# esp_LedControl_signal.net
KiCad netlist of a schematic drawn in EAGLE
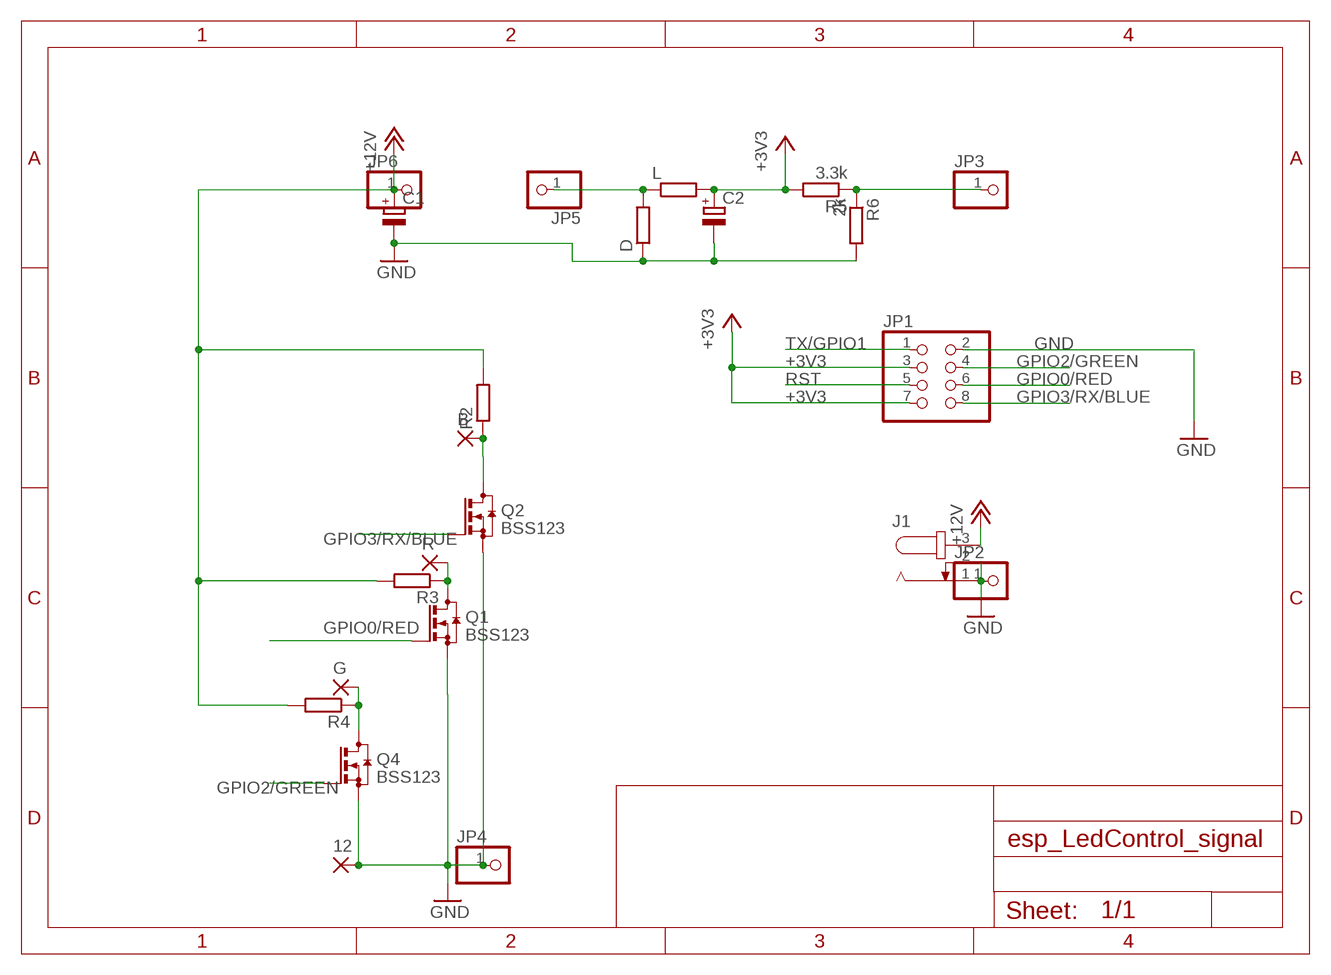
[diagram p0: schematic, sheet 1]

(export (version "E")
  (design (tool "Eeschema 10.0.6"))
  (components
    (comp (ref "12")
      (value "3,17/1,3")
      (footprint "eagle-import:3,17_1,3")
      (libsource (lib "eagle-import") (part "3,17/1,3"))
    )
    (comp (ref "B")
      (value "3,17/1,3")
      (footprint "eagle-import:3,17_1,3")
      (libsource (lib "eagle-import") (part "3,17/1,3"))
    )
    (comp (ref "C1")
      (value "CPOL-EUE2.5-5")
      (footprint "eagle-import:E2,5-5")
      (libsource (lib "eagle-import") (part "CPOL-EUE2.5-5"))
    )
    (comp (ref "C2")
      (value "CPOL-EUE2.5-5")
      (footprint "eagle-import:E2,5-5")
      (libsource (lib "eagle-import") (part "CPOL-EUE2.5-5"))
    )
    (comp (ref "D")
      (value "R-EU_0204/7")
      (footprint "eagle-import:0204_7")
      (libsource (lib "eagle-import") (part "R-EU_0204/7"))
    )
    (comp (ref "G")
      (value "3,17/1,3")
      (footprint "eagle-import:3,17_1,3")
      (libsource (lib "eagle-import") (part "3,17/1,3"))
    )
    (comp (ref "J1")
      (value "JACK-PLUG0")
      (footprint "eagle-import:SPC4077")
      (libsource (lib "eagle-import") (part "JACK-PLUG0"))
    )
    (comp (ref "JP1")
      (value "PINHD-2X4")
      (footprint "eagle-import:2X04")
      (libsource (lib "eagle-import") (part "PINHD-2X4"))
    )
    (comp (ref "JP2")
      (value "PINHD-1X1")
      (footprint "eagle-import:1X01")
      (libsource (lib "eagle-import") (part "PINHD-1X1"))
    )
    (comp (ref "JP3")
      (value "PINHD-1X1")
      (footprint "eagle-import:1X01")
      (libsource (lib "eagle-import") (part "PINHD-1X1"))
    )
    (comp (ref "JP4")
      (value "PINHD-1X1")
      (footprint "eagle-import:1X01")
      (libsource (lib "eagle-import") (part "PINHD-1X1"))
    )
    (comp (ref "JP5")
      (value "PINHD-1X1")
      (footprint "eagle-import:1X01")
      (libsource (lib "eagle-import") (part "PINHD-1X1"))
    )
    (comp (ref "JP6")
      (value "PINHD-1X1")
      (footprint "eagle-import:1X01")
      (libsource (lib "eagle-import") (part "PINHD-1X1"))
    )
    (comp (ref "L")
      (value "R-EU_0204/7")
      (footprint "eagle-import:0204_7")
      (libsource (lib "eagle-import") (part "R-EU_0204/7"))
    )
    (comp (ref "Q1")
      (value "BSS123")
      (footprint "eagle-import:SOT23")
      (libsource (lib "eagle-import") (part "BSS123"))
    )
    (comp (ref "Q2")
      (value "BSS123")
      (footprint "eagle-import:SOT23")
      (libsource (lib "eagle-import") (part "BSS123"))
    )
    (comp (ref "Q4")
      (value "BSS123")
      (footprint "eagle-import:SOT23")
      (libsource (lib "eagle-import") (part "BSS123"))
    )
    (comp (ref "R")
      (value "3,17/1,3")
      (footprint "eagle-import:3,17_1,3")
      (libsource (lib "eagle-import") (part "3,17/1,3"))
    )
    (comp (ref "R2")
      (value "R-EU_R0805")
      (footprint "eagle-import:R0805")
      (libsource (lib "eagle-import") (part "R-EU_R0805"))
    )
    (comp (ref "R3")
      (value "R-EU_R0805")
      (footprint "eagle-import:R0805")
      (libsource (lib "eagle-import") (part "R-EU_R0805"))
    )
    (comp (ref "R4")
      (value "R-EU_R0805")
      (footprint "eagle-import:R0805")
      (libsource (lib "eagle-import") (part "R-EU_R0805"))
    )
    (comp (ref "R5")
      (value "3.3k")
      (footprint "eagle-import:R1206")
      (libsource (lib "eagle-import") (part "R-EU_R1206"))
    )
    (comp (ref "R6")
      (value "2k")
      (footprint "eagle-import:R1206")
      (libsource (lib "eagle-import") (part "R-EU_R1206"))
    )
  )
  (nets
    (net (code "1") (name "+3V3") (class "Default")
      (node (ref "C2") (pin "+") (pinfunction "+_+") (pintype "passive"))
      (node (ref "JP1") (pin "3") (pinfunction "3_3") (pintype "passive"))
      (node (ref "JP1") (pin "7") (pinfunction "7_7") (pintype "passive"))
      (node (ref "L") (pin "2") (pinfunction "2_2") (pintype "passive"))
      (node (ref "R5") (pin "2") (pinfunction "2_2") (pintype "passive"))
    )
    (net (code "2") (name "+12V") (class "Default")
      (node (ref "C1") (pin "+") (pinfunction "+_+") (pintype "passive"))
      (node (ref "J1") (pin "3") (pinfunction "3_3") (pintype "passive"))
      (node (ref "JP6") (pin "1") (pinfunction "1_1") (pintype "passive"))
      (node (ref "R2") (pin "2") (pinfunction "2_2") (pintype "passive"))
      (node (ref "R3") (pin "2") (pinfunction "2_2") (pintype "passive"))
      (node (ref "R4") (pin "2") (pinfunction "2_2") (pintype "passive"))
    )
    (net (code "3") (name "/GPIO0{slash}RED") (class "Default")
      (node (ref "JP1") (pin "6") (pinfunction "6_6") (pintype "passive"))
      (node (ref "Q1") (pin "1") (pinfunction "G_1") (pintype "passive"))
    )
    (net (code "4") (name "/GPIO2{slash}GREEN") (class "Default")
      (node (ref "JP1") (pin "4") (pinfunction "4_4") (pintype "passive"))
      (node (ref "Q4") (pin "1") (pinfunction "G_1") (pintype "passive"))
    )
    (net (code "5") (name "/GPIO3{slash}RX{slash}BLUE") (class "Default")
      (node (ref "JP1") (pin "8") (pinfunction "8_8") (pintype "passive"))
      (node (ref "Q2") (pin "1") (pinfunction "G_1") (pintype "passive"))
    )
    (net (code "6") (name "/RST") (class "Default")
      (node (ref "JP1") (pin "5") (pinfunction "5_5") (pintype "passive"))
    )
    (net (code "7") (name "/TX{slash}GPIO1") (class "Default")
      (node (ref "JP1") (pin "1") (pinfunction "1_1") (pintype "passive"))
    )
    (net (code "8") (name "GND") (class "Default")
      (node (ref "12") (pin "1") (pinfunction "P_1") (pintype "passive"))
      (node (ref "C1") (pin "-") (pinfunction "-_-") (pintype "passive"))
      (node (ref "C2") (pin "-") (pinfunction "-_-") (pintype "passive"))
      (node (ref "D") (pin "1") (pinfunction "1_1") (pintype "passive"))
      (node (ref "J1") (pin "1") (pinfunction "1_1") (pintype "passive"))
      (node (ref "J1") (pin "2") (pinfunction "2_2") (pintype "passive"))
      (node (ref "JP1") (pin "2") (pinfunction "2_2") (pintype "passive"))
      (node (ref "JP2") (pin "1") (pinfunction "1_1") (pintype "passive"))
      (node (ref "JP4") (pin "1") (pinfunction "1_1") (pintype "passive"))
      (node (ref "Q1") (pin "2") (pinfunction "S_2") (pintype "passive"))
      (node (ref "Q2") (pin "2") (pinfunction "S_2") (pintype "passive"))
      (node (ref "Q4") (pin "2") (pinfunction "S_2") (pintype "passive"))
      (node (ref "R6") (pin "2") (pinfunction "2_2") (pintype "passive"))
    )
    (net (code "9") (name "Net-(B-P)") (class "Default")
      (node (ref "B") (pin "1") (pinfunction "P_1") (pintype "passive"))
      (node (ref "Q2") (pin "3") (pinfunction "D_3") (pintype "passive"))
      (node (ref "R2") (pin "1") (pinfunction "1_1") (pintype "passive"))
    )
    (net (code "10") (name "Net-(D-Pad2)") (class "Default")
      (node (ref "D") (pin "2") (pinfunction "2_2") (pintype "passive"))
      (node (ref "JP5") (pin "1") (pinfunction "1_1") (pintype "passive"))
      (node (ref "L") (pin "1") (pinfunction "1_1") (pintype "passive"))
    )
    (net (code "11") (name "Net-(G-P)") (class "Default")
      (node (ref "G") (pin "1") (pinfunction "P_1") (pintype "passive"))
      (node (ref "Q4") (pin "3") (pinfunction "D_3") (pintype "passive"))
      (node (ref "R4") (pin "1") (pinfunction "1_1") (pintype "passive"))
    )
    (net (code "12") (name "Net-(JP3-Pad1)") (class "Default")
      (node (ref "JP3") (pin "1") (pinfunction "1_1") (pintype "passive"))
      (node (ref "R5") (pin "1") (pinfunction "1_1") (pintype "passive"))
      (node (ref "R6") (pin "1") (pinfunction "1_1") (pintype "passive"))
    )
    (net (code "13") (name "Net-(Q1-D)") (class "Default")
      (node (ref "Q1") (pin "3") (pinfunction "D_3") (pintype "passive"))
      (node (ref "R") (pin "1") (pinfunction "P_1") (pintype "passive"))
      (node (ref "R3") (pin "1") (pinfunction "1_1") (pintype "passive"))
    )
  )
)
